# Sheet2.net
KiCad netlist of a schematic drawn in Altium Designer
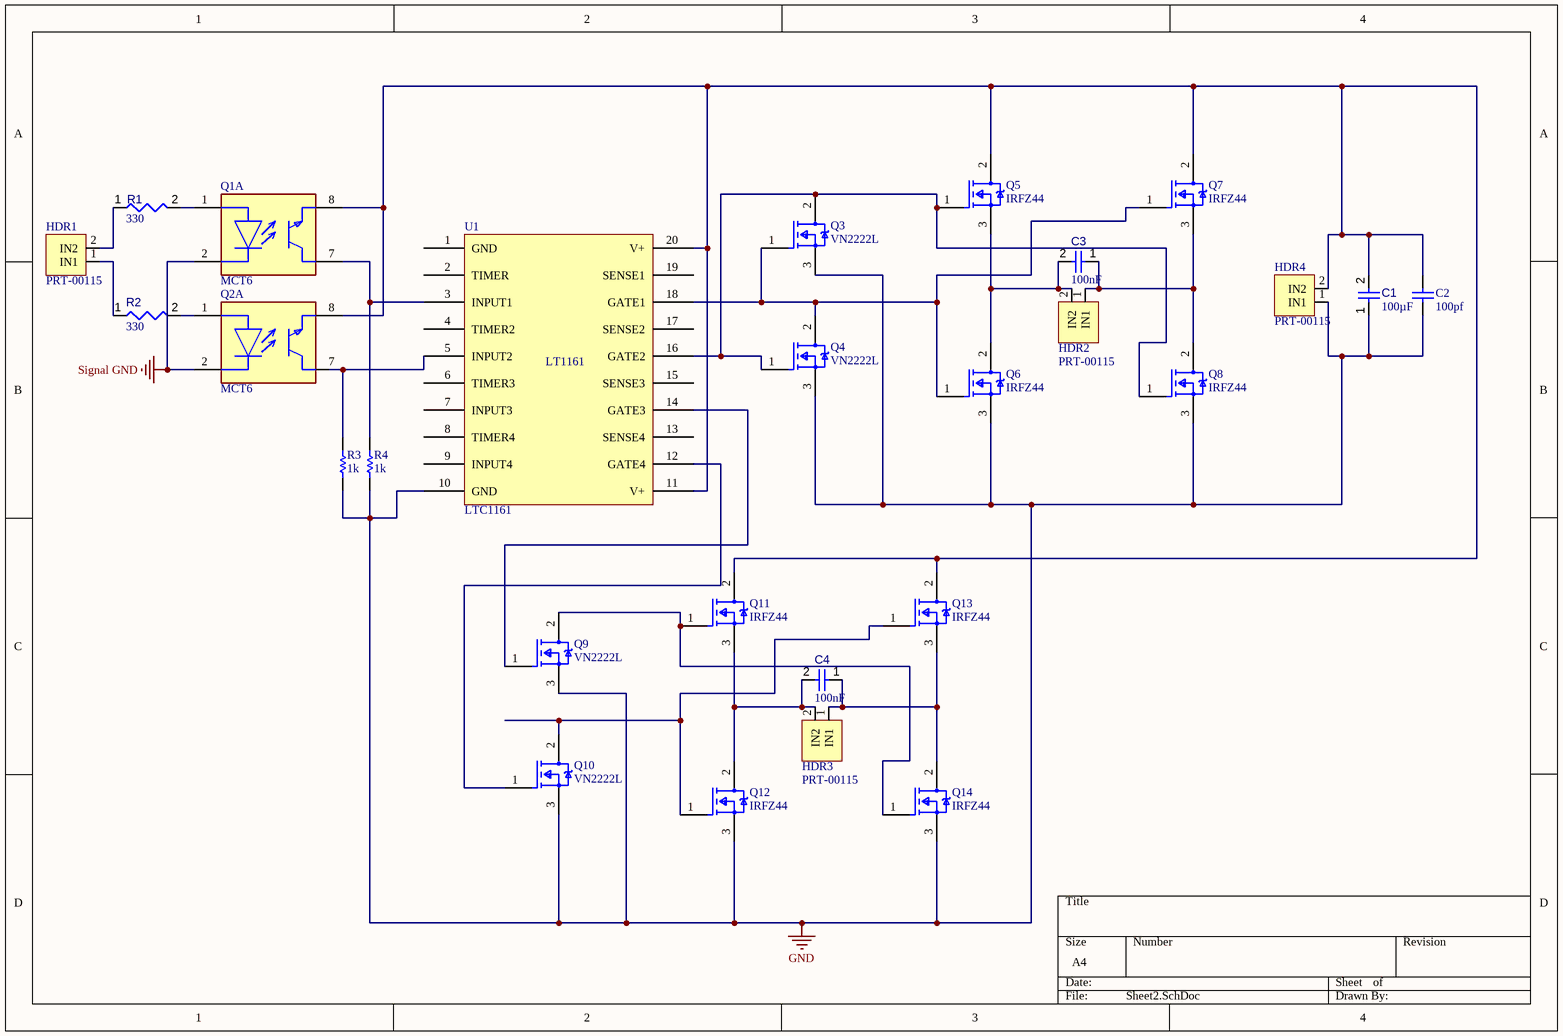
[diagram p0: Sheet2.SchDoc]

(export (version "E")
  (design (tool "Eeschema 10.0.6"))
  (components
    (comp (ref "C1")
      (value "100µF")
      (footprint "CAPC3216X190X55LL30T25")
      (description "Chip Capacitor, 100 uF, +/- 20%, 6.3 V, 1206 (3216 Metric)")
      (fields (field (name "TOLERANCE") "20%") (field (name "Comment") "Capacitor 100 uF +/- 20% 6.3 V 1206"))
      (libsource (lib "Workspace") (part "CAP-NP-2"))
    )
    (comp (ref "C2")
      (value "100pf")
      (footprint "CAPC1608X90X40ML10T20")
      (description "Chip Capacitor, 100 pF, +/- 5%, 50 V, -55 to 125 degC, 0603 (1608 Metric), RoHS, Tape and Reel")
      (fields (field (name "TOLERANCE") "5%") (field (name "VOLTAGE") "50V"))
      (libsource (lib "Altium Content Vault") (part "CAP-NP-2"))
    )
    (comp (ref "C3")
      (value "100nF")
      (footprint "CAPC0402(1005)60_L")
      (description "Chip Capacitor, 100nF +/-20%, 10V, 0402, Thickness 0.6 mm")
      (fields (field (name "TOLERANCE") "20%") (field (name "Comment") "Capacitor 100nF +/-20% 10V 0402"))
      (libsource (lib "Workspace") (part "CAP-NP-2"))
    )
    (comp (ref "C4")
      (value "100nF")
      (footprint "CAPC0402(1005)60_L")
      (description "Chip Capacitor, 100nF +/-20%, 10V, 0402, Thickness 0.6 mm")
      (fields (field (name "TOLERANCE") "20%") (field (name "Comment") "Capacitor 100nF +/-20% 10V 0402"))
      (libsource (lib "Workspace") (part "CAP-NP-2"))
    )
    (comp (ref "HDR1") (value "PRT-00115") (libsource (lib "Schlib1") (part "PRT-00115")))
    (comp (ref "HDR2") (value "PRT-00115") (libsource (lib "") (part "PRT-00115_1")))
    (comp (ref "HDR3") (value "PRT-00115") (libsource (lib "") (part "PRT-00115_1")))
    (comp (ref "HDR4") (value "PRT-00115") (libsource (lib "Schlib1") (part "PRT-00115")))
    (comp (ref "Q1")
      (value "MCT6")
      (footprint "FP-646CQ-MFG")
      (description "MCT6 Optocoupler DC-IN 2-CH Transistor DC-OUT 8-Pin PDIP Black Bulk - Rail/Tube")
      (libsource (lib "Altium Content Vault") (part "4fabb46c152c9b017256a501a602342"))
    )
    (comp (ref "Q2")
      (value "MCT6")
      (footprint "FP-646CQ-MFG")
      (description "MCT6 Optocoupler DC-IN 2-CH Transistor DC-OUT 8-Pin PDIP Black Bulk - Rail/Tube")
      (libsource (lib "Altium Content Vault") (part "4fabb46c152c9b017256a501a602342"))
    )
    (comp (ref "Q3")
      (value "VN2222L")
      (footprint "FP-PG-TO220-3-MFG")
      (description "MOSFET N-CH 60V 55A TO220AB")
      (libsource (lib "Altium Content Vault") (part "8b62d417cbef8344eebe0bde0c45977"))
    )
    (comp (ref "Q4")
      (value "VN2222L")
      (footprint "FP-PG-TO220-3-MFG")
      (description "MOSFET N-CH 60V 55A TO220AB")
      (libsource (lib "Altium Content Vault") (part "8b62d417cbef8344eebe0bde0c45977"))
    )
    (comp (ref "Q5")
      (value "IRFZ44")
      (footprint "FP-PG-TO220-3-MFG")
      (description "MOSFET N-CH 60V 55A TO220AB")
      (libsource (lib "Altium Content Vault") (part "8b62d417cbef8344eebe0bde0c45977"))
    )
    (comp (ref "Q6")
      (value "IRFZ44")
      (footprint "FP-PG-TO220-3-MFG")
      (description "MOSFET N-CH 60V 55A TO220AB")
      (libsource (lib "Altium Content Vault") (part "8b62d417cbef8344eebe0bde0c45977"))
    )
    (comp (ref "Q7")
      (value "IRFZ44")
      (footprint "FP-PG-TO220-3-MFG")
      (description "MOSFET N-CH 60V 55A TO220AB")
      (libsource (lib "Altium Content Vault") (part "8b62d417cbef8344eebe0bde0c45977"))
    )
    (comp (ref "Q8")
      (value "IRFZ44")
      (footprint "FP-PG-TO220-3-MFG")
      (description "MOSFET N-CH 60V 55A TO220AB")
      (libsource (lib "Altium Content Vault") (part "8b62d417cbef8344eebe0bde0c45977"))
    )
    (comp (ref "Q9")
      (value "VN2222L")
      (footprint "FP-PG-TO220-3-MFG")
      (description "MOSFET N-CH 60V 55A TO220AB")
      (libsource (lib "Altium Content Vault") (part "8b62d417cbef8344eebe0bde0c45977"))
    )
    (comp (ref "Q10")
      (value "VN2222L")
      (footprint "FP-PG-TO220-3-MFG")
      (description "MOSFET N-CH 60V 55A TO220AB")
      (libsource (lib "Altium Content Vault") (part "8b62d417cbef8344eebe0bde0c45977"))
    )
    (comp (ref "Q11")
      (value "IRFZ44")
      (footprint "FP-PG-TO220-3-MFG")
      (description "MOSFET N-CH 60V 55A TO220AB")
      (libsource (lib "Altium Content Vault") (part "8b62d417cbef8344eebe0bde0c45977"))
    )
    (comp (ref "Q12")
      (value "IRFZ44")
      (footprint "FP-PG-TO220-3-MFG")
      (description "MOSFET N-CH 60V 55A TO220AB")
      (libsource (lib "Altium Content Vault") (part "8b62d417cbef8344eebe0bde0c45977"))
    )
    (comp (ref "Q13")
      (value "IRFZ44")
      (footprint "FP-PG-TO220-3-MFG")
      (description "MOSFET N-CH 60V 55A TO220AB")
      (libsource (lib "Altium Content Vault") (part "8b62d417cbef8344eebe0bde0c45977"))
    )
    (comp (ref "Q14")
      (value "IRFZ44")
      (footprint "FP-PG-TO220-3-MFG")
      (description "MOSFET N-CH 60V 55A TO220AB")
      (libsource (lib "Altium Content Vault") (part "8b62d417cbef8344eebe0bde0c45977"))
    )
    (comp (ref "R1")
      (value "330")
      (footprint "RESC0402(1005)_L")
      (description "Chip Resistor, 330 Ohms, +/-5 %, 63 mW, -55 to 155 degC, 0402")
      (fields (field (name "POWER") "63mW") (field (name "TOLERANCE") "5%"))
      (libsource (lib "") (part "RES-2_1"))
    )
    (comp (ref "R2")
      (value "330")
      (footprint "RESC0402(1005)_L")
      (description "Chip Resistor, 330 Ohms, +/-5 %, 63 mW, -55 to 155 degC, 0402")
      (fields (field (name "POWER") "63mW") (field (name "TOLERANCE") "5%"))
      (libsource (lib "") (part "RES-2_1"))
    )
    (comp (ref "R3")
      (value "1k")
      (footprint "RESC3116X70X50ML13T20")
      (description "Chip Resistor, 1 KOhm, +/- 1%, 0.25 W, -55 to 155 degC, 1206 (3216 Metric)")
      (fields (field (name "TOLERANCE") "1%") (field (name "POWER") "250mW"))
      (libsource (lib "Workspace") (part "RES-2"))
    )
    (comp (ref "R4")
      (value "1k")
      (footprint "RESC3116X70X50ML13T20")
      (description "Chip Resistor, 1 KOhm, +/- 1%, 0.25 W, -55 to 155 degC, 1206 (3216 Metric)")
      (fields (field (name "TOLERANCE") "1%") (field (name "POWER") "250mW"))
      (libsource (lib "Workspace") (part "RES-2"))
    )
    (comp (ref "U1") (value "LTC1161") (libsource (lib "Schlib1") (part "LTC1161")))
  )
  (nets
    (net (code "1") (name "GND") (class "Default")
      (node (ref "C1") (pin "1") (pinfunction "1_1") (pintype "passive"))
      (node (ref "C2") (pin "1") (pinfunction "1_1") (pintype "passive"))
      (node (ref "HDR4") (pin "1") (pinfunction "IN1_1") (pintype "passive"))
      (node (ref "Q10") (pin "3") (pinfunction "SOURCE_3") (pintype "passive"))
      (node (ref "Q12") (pin "3") (pinfunction "SOURCE_3") (pintype "passive"))
      (node (ref "Q14") (pin "3") (pinfunction "SOURCE_3") (pintype "passive"))
      (node (ref "Q3") (pin "3") (pinfunction "SOURCE_3") (pintype "passive"))
      (node (ref "Q4") (pin "3") (pinfunction "SOURCE_3") (pintype "passive"))
      (node (ref "Q6") (pin "3") (pinfunction "SOURCE_3") (pintype "passive"))
      (node (ref "Q8") (pin "3") (pinfunction "SOURCE_3") (pintype "passive"))
      (node (ref "Q9") (pin "3") (pinfunction "SOURCE_3") (pintype "passive"))
      (node (ref "R3") (pin "1") (pinfunction "1_1") (pintype "passive"))
      (node (ref "R4") (pin "1") (pinfunction "1_1") (pintype "passive"))
      (node (ref "U1") (pin "10") (pinfunction "GND_10") (pintype "passive"))
    )
    (net (code "2") (name "Net-(HDR1-IN1)") (class "Default")
      (node (ref "HDR1") (pin "1") (pinfunction "IN1_1") (pintype "passive"))
      (node (ref "R2") (pin "1") (pinfunction "1_1") (pintype "passive"))
    )
    (net (code "3") (name "Net-(HDR1-IN2)") (class "Default")
      (node (ref "HDR1") (pin "2") (pinfunction "IN2_2") (pintype "passive"))
      (node (ref "R1") (pin "1") (pinfunction "1_1") (pintype "passive"))
    )
    (net (code "4") (name "Net-(HDR2-IN1)") (class "Default")
      (node (ref "C3") (pin "1") (pinfunction "1_1") (pintype "passive"))
      (node (ref "HDR2") (pin "1") (pinfunction "IN1_1") (pintype "passive"))
      (node (ref "Q7") (pin "3") (pinfunction "SOURCE_3") (pintype "passive"))
      (node (ref "Q8") (pin "2") (pinfunction "DRAIN_2") (pintype "passive"))
    )
    (net (code "5") (name "Net-(HDR2-IN2)") (class "Default")
      (node (ref "C3") (pin "2") (pinfunction "2_2") (pintype "passive"))
      (node (ref "HDR2") (pin "2") (pinfunction "IN2_2") (pintype "passive"))
      (node (ref "Q5") (pin "3") (pinfunction "SOURCE_3") (pintype "passive"))
      (node (ref "Q6") (pin "2") (pinfunction "DRAIN_2") (pintype "passive"))
    )
    (net (code "6") (name "Net-(HDR3-IN1)") (class "Default")
      (node (ref "C4") (pin "1") (pinfunction "1_1") (pintype "passive"))
      (node (ref "HDR3") (pin "1") (pinfunction "IN1_1") (pintype "passive"))
      (node (ref "Q13") (pin "3") (pinfunction "SOURCE_3") (pintype "passive"))
      (node (ref "Q14") (pin "2") (pinfunction "DRAIN_2") (pintype "passive"))
    )
    (net (code "7") (name "Net-(HDR3-IN2)") (class "Default")
      (node (ref "C4") (pin "2") (pinfunction "2_2") (pintype "passive"))
      (node (ref "HDR3") (pin "2") (pinfunction "IN2_2") (pintype "passive"))
      (node (ref "Q11") (pin "3") (pinfunction "SOURCE_3") (pintype "passive"))
      (node (ref "Q12") (pin "2") (pinfunction "DRAIN_2") (pintype "passive"))
    )
    (net (code "8") (name "Net-(HDR4-IN2)") (class "Default")
      (node (ref "C1") (pin "2") (pinfunction "2_2") (pintype "passive"))
      (node (ref "C2") (pin "2") (pinfunction "2_2") (pintype "passive"))
      (node (ref "HDR4") (pin "2") (pinfunction "IN2_2") (pintype "passive"))
      (node (ref "Q1") (pin "8") (pinfunction "E_8") (pintype "passive"))
      (node (ref "Q11") (pin "2") (pinfunction "DRAIN_2") (pintype "passive"))
      (node (ref "Q13") (pin "2") (pinfunction "DRAIN_2") (pintype "passive"))
      (node (ref "Q2") (pin "8") (pinfunction "E_8") (pintype "passive"))
      (node (ref "Q5") (pin "2") (pinfunction "DRAIN_2") (pintype "passive"))
      (node (ref "Q7") (pin "2") (pinfunction "DRAIN_2") (pintype "passive"))
      (node (ref "U1") (pin "11") (pinfunction "V+_11") (pintype "passive"))
      (node (ref "U1") (pin "20") (pinfunction "V+_20") (pintype "passive"))
    )
    (net (code "9") (name "Net-(Q1A-1_ANODE)") (class "Default")
      (node (ref "Q1") (pin "1") (pinfunction "1_ANODE_1") (pintype "passive"))
      (node (ref "R1") (pin "2") (pinfunction "2_2") (pintype "passive"))
    )
    (net (code "10") (name "Net-(Q1A-C)") (class "Default")
      (node (ref "Q1") (pin "7") (pinfunction "C_7") (pintype "passive"))
      (node (ref "R4") (pin "2") (pinfunction "2_2") (pintype "passive"))
      (node (ref "U1") (pin "3") (pinfunction "INPUT1_3") (pintype "passive"))
    )
    (net (code "11") (name "Net-(Q2A-1_ANODE)") (class "Default")
      (node (ref "Q2") (pin "1") (pinfunction "1_ANODE_1") (pintype "passive"))
      (node (ref "R2") (pin "2") (pinfunction "2_2") (pintype "passive"))
    )
    (net (code "12") (name "Net-(Q2A-C)") (class "Default")
      (node (ref "Q2") (pin "7") (pinfunction "C_7") (pintype "passive"))
      (node (ref "R3") (pin "2") (pinfunction "2_2") (pintype "passive"))
      (node (ref "U1") (pin "5") (pinfunction "INPUT2_5") (pintype "passive"))
    )
    (net (code "13") (name "Net-(Q3-DRAIN)") (class "Default")
      (node (ref "Q3") (pin "2") (pinfunction "DRAIN_2") (pintype "passive"))
      (node (ref "Q4") (pin "1") (pinfunction "GATE_1") (pintype "passive"))
      (node (ref "Q5") (pin "1") (pinfunction "GATE_1") (pintype "passive"))
      (node (ref "Q8") (pin "1") (pinfunction "GATE_1") (pintype "passive"))
      (node (ref "U1") (pin "16") (pinfunction "GATE2_16") (pintype "passive"))
    )
    (net (code "14") (name "Net-(Q3-GATE)") (class "Default")
      (node (ref "Q3") (pin "1") (pinfunction "GATE_1") (pintype "passive"))
      (node (ref "Q4") (pin "2") (pinfunction "DRAIN_2") (pintype "passive"))
      (node (ref "Q6") (pin "1") (pinfunction "GATE_1") (pintype "passive"))
      (node (ref "Q7") (pin "1") (pinfunction "GATE_1") (pintype "passive"))
      (node (ref "U1") (pin "18") (pinfunction "GATE1_18") (pintype "passive"))
    )
    (net (code "15") (name "Net-(Q9-GATE)") (class "Default")
      (node (ref "Q9") (pin "1") (pinfunction "GATE_1") (pintype "passive"))
      (node (ref "U1") (pin "14") (pinfunction "GATE3_14") (pintype "passive"))
    )
    (net (code "16") (name "Net-(Q10-DRAIN)") (class "Default")
      (node (ref "Q10") (pin "2") (pinfunction "DRAIN_2") (pintype "passive"))
      (node (ref "Q12") (pin "1") (pinfunction "GATE_1") (pintype "passive"))
      (node (ref "Q13") (pin "1") (pinfunction "GATE_1") (pintype "passive"))
    )
    (net (code "17") (name "Net-(Q10-GATE)") (class "Default")
      (node (ref "Q10") (pin "1") (pinfunction "GATE_1") (pintype "passive"))
      (node (ref "U1") (pin "12") (pinfunction "GATE4_12") (pintype "passive"))
    )
    (net (code "18") (name "Net-(Q11-GATE)") (class "Default")
      (node (ref "Q11") (pin "1") (pinfunction "GATE_1") (pintype "passive"))
      (node (ref "Q14") (pin "1") (pinfunction "GATE_1") (pintype "passive"))
      (node (ref "Q9") (pin "2") (pinfunction "DRAIN_2") (pintype "passive"))
    )
    (net (code "19") (name "Signal GND") (class "Default")
      (node (ref "Q1") (pin "2") (pinfunction "1_CATHODE_2") (pintype "passive"))
      (node (ref "Q2") (pin "2") (pinfunction "1_CATHODE_2") (pintype "passive"))
    )
    (net (code "20") (name "unconnected-(U1-GND-Pad1)") (class "Default")
      (node (ref "U1") (pin "1") (pinfunction "GND_1") (pintype "passive"))
    )
    (net (code "21") (name "unconnected-(U1-INPUT3-Pad7)") (class "Default")
      (node (ref "U1") (pin "7") (pinfunction "INPUT3_7") (pintype "passive"))
    )
    (net (code "22") (name "unconnected-(U1-INPUT4-Pad9)") (class "Default")
      (node (ref "U1") (pin "9") (pinfunction "INPUT4_9") (pintype "passive"))
    )
    (net (code "23") (name "unconnected-(U1-SENSE1-Pad19)") (class "Default")
      (node (ref "U1") (pin "19") (pinfunction "SENSE1_19") (pintype "passive"))
    )
    (net (code "24") (name "unconnected-(U1-SENSE2-Pad17)") (class "Default")
      (node (ref "U1") (pin "17") (pinfunction "SENSE2_17") (pintype "passive"))
    )
    (net (code "25") (name "unconnected-(U1-SENSE3-Pad15)") (class "Default")
      (node (ref "U1") (pin "15") (pinfunction "SENSE3_15") (pintype "passive"))
    )
    (net (code "26") (name "unconnected-(U1-SENSE4-Pad13)") (class "Default")
      (node (ref "U1") (pin "13") (pinfunction "SENSE4_13") (pintype "passive"))
    )
    (net (code "27") (name "unconnected-(U1-TIMER-Pad2)") (class "Default")
      (node (ref "U1") (pin "2") (pinfunction "TIMER_2") (pintype "passive"))
    )
    (net (code "28") (name "unconnected-(U1-TIMER2-Pad4)") (class "Default")
      (node (ref "U1") (pin "4") (pinfunction "TIMER2_4") (pintype "passive"))
    )
    (net (code "29") (name "unconnected-(U1-TIMER3-Pad6)") (class "Default")
      (node (ref "U1") (pin "6") (pinfunction "TIMER3_6") (pintype "passive"))
    )
    (net (code "30") (name "unconnected-(U1-TIMER4-Pad8)") (class "Default")
      (node (ref "U1") (pin "8") (pinfunction "TIMER4_8") (pintype "passive"))
    )
  )
)
